# carlos_reg_psu.net
KiCad netlist of a schematic drawn in EAGLE
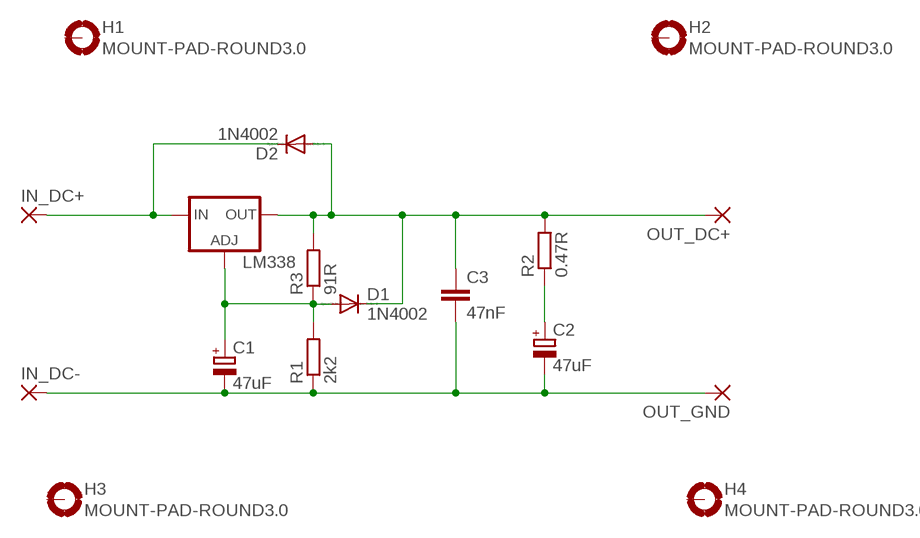
[diagram p0: schematic, sheet 1]

(export (version "E")
  (design (tool "Eeschema 10.0.6"))
  (components
    (comp (ref "C1")
      (value "47uF")
      (footprint "eagle-import:E5-13")
      (libsource (lib "eagle-import") (part "CPOL-EUE5-13"))
    )
    (comp (ref "C2")
      (value "47uF")
      (footprint "eagle-import:E5-13")
      (libsource (lib "eagle-import") (part "CPOL-EUE5-13"))
    )
    (comp (ref "C3")
      (value "47nF")
      (footprint "eagle-import:C050-030X075")
      (libsource (lib "eagle-import") (part "C-EU050-030X075"))
    )
    (comp (ref "D1")
      (value "1N4002")
      (footprint "eagle-import:DO41-10")
      (libsource (lib "eagle-import") (part "1N4004"))
    )
    (comp (ref "D2")
      (value "1N4002")
      (footprint "eagle-import:DO41-10")
      (libsource (lib "eagle-import") (part "1N4004"))
    )
    (comp (ref "H1")
      (value "MOUNT-PAD-ROUND3.0")
      (footprint "eagle-import:3,0-PAD")
      (libsource (lib "eagle-import") (part "MOUNT-PAD-ROUND3.0"))
    )
    (comp (ref "H2")
      (value "MOUNT-PAD-ROUND3.0")
      (footprint "eagle-import:3,0-PAD")
      (libsource (lib "eagle-import") (part "MOUNT-PAD-ROUND3.0"))
    )
    (comp (ref "H3")
      (value "MOUNT-PAD-ROUND3.0")
      (footprint "eagle-import:3,0-PAD")
      (libsource (lib "eagle-import") (part "MOUNT-PAD-ROUND3.0"))
    )
    (comp (ref "H4")
      (value "MOUNT-PAD-ROUND3.0")
      (footprint "eagle-import:3,0-PAD")
      (libsource (lib "eagle-import") (part "MOUNT-PAD-ROUND3.0"))
    )
    (comp (ref "IN_DC+")
      (value "2,54/1,0")
      (footprint "eagle-import:2,54_1,0")
      (libsource (lib "eagle-import") (part "2,54/1,0"))
    )
    (comp (ref "IN_DC-")
      (value "2,54/1,0")
      (footprint "eagle-import:2,54_1,0")
      (libsource (lib "eagle-import") (part "2,54/1,0"))
    )
    (comp (ref "LM338")
      (value "LM317TS")
      (footprint "eagle-import:317TS")
      (libsource (lib "eagle-import") (part "LM317TS"))
    )
    (comp (ref "OUT_DC+")
      (value "2,54/1,0")
      (footprint "eagle-import:2,54_1,0")
      (libsource (lib "eagle-import") (part "2,54/1,0"))
    )
    (comp (ref "OUT_GND")
      (value "2,54/1,0")
      (footprint "eagle-import:2,54_1,0")
      (libsource (lib "eagle-import") (part "2,54/1,0"))
    )
    (comp (ref "R1")
      (value "2k2")
      (footprint "eagle-import:0414V")
      (libsource (lib "eagle-import") (part "R-EU_0414/5V"))
    )
    (comp (ref "R2")
      (value "0.47R")
      (footprint "eagle-import:0414V")
      (libsource (lib "eagle-import") (part "R-EU_0414/5V"))
    )
    (comp (ref "R3")
      (value "91R")
      (footprint "eagle-import:0414V")
      (libsource (lib "eagle-import") (part "R-EU_0414/5V"))
    )
  )
  (nets
    (net (code "1") (name "Net-(C2-Pad+)") (class "Default")
      (node (ref "C2") (pin "+") (pinfunction "+_+") (pintype "passive"))
      (node (ref "R2") (pin "1") (pinfunction "1_1") (pintype "passive"))
    )
    (net (code "2") (name "Net-(IN_DC+-P)") (class "Default")
      (node (ref "D2") (pin "C") (pinfunction "C_C") (pintype "passive"))
      (node (ref "IN_DC+") (pin "1") (pinfunction "P_1") (pintype "passive"))
      (node (ref "LM338") (pin "3") (pinfunction "IN_3") (pintype "input"))
    )
    (net (code "3") (name "Net-(IN_DC--P)") (class "Default")
      (node (ref "C1") (pin "-") (pinfunction "-_-") (pintype "passive"))
      (node (ref "C2") (pin "-") (pinfunction "-_-") (pintype "passive"))
      (node (ref "C3") (pin "2") (pinfunction "2_2") (pintype "passive"))
      (node (ref "IN_DC-") (pin "1") (pinfunction "P_1") (pintype "passive"))
      (node (ref "OUT_GND") (pin "1") (pinfunction "P_1") (pintype "passive"))
      (node (ref "R1") (pin "1") (pinfunction "1_1") (pintype "passive"))
    )
    (net (code "4") (name "Net-(LM338-ADJ)") (class "Default")
      (node (ref "C1") (pin "+") (pinfunction "+_+") (pintype "passive"))
      (node (ref "D1") (pin "A") (pinfunction "A_A") (pintype "passive"))
      (node (ref "LM338") (pin "1") (pinfunction "ADJ_1") (pintype "input"))
      (node (ref "R1") (pin "2") (pinfunction "2_2") (pintype "passive"))
      (node (ref "R3") (pin "1") (pinfunction "1_1") (pintype "passive"))
    )
    (net (code "5") (name "Net-(LM338-OUT)") (class "Default")
      (node (ref "C3") (pin "1") (pinfunction "1_1") (pintype "passive"))
      (node (ref "D1") (pin "C") (pinfunction "C_C") (pintype "passive"))
      (node (ref "D2") (pin "A") (pinfunction "A_A") (pintype "passive"))
      (node (ref "LM338") (pin "2") (pinfunction "OUT_2") (pintype "passive"))
      (node (ref "OUT_DC+") (pin "1") (pinfunction "P_1") (pintype "passive"))
      (node (ref "R2") (pin "2") (pinfunction "2_2") (pintype "passive"))
      (node (ref "R3") (pin "2") (pinfunction "2_2") (pintype "passive"))
    )
    (net (code "6") (name "unconnected-(H1-MOUNT-PadB3,0)") (class "Default")
      (node (ref "H1") (pin "B3,0") (pinfunction "MOUNT_B3,0") (pintype "passive"))
    )
    (net (code "7") (name "unconnected-(H2-MOUNT-PadB3,0)") (class "Default")
      (node (ref "H2") (pin "B3,0") (pinfunction "MOUNT_B3,0") (pintype "passive"))
    )
    (net (code "8") (name "unconnected-(H3-MOUNT-PadB3,0)") (class "Default")
      (node (ref "H3") (pin "B3,0") (pinfunction "MOUNT_B3,0") (pintype "passive"))
    )
    (net (code "9") (name "unconnected-(H4-MOUNT-PadB3,0)") (class "Default")
      (node (ref "H4") (pin "B3,0") (pinfunction "MOUNT_B3,0") (pintype "passive"))
    )
  )
)
